# Timer.net
KiCad netlist of a schematic drawn in EAGLE
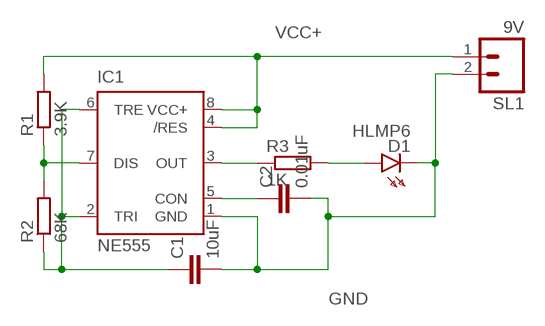
[diagram p0: schematic, sheet 1]

(export (version "E")
  (design (tool "Eeschema 10.0.6"))
  (components
    (comp (ref "C1")
      (value "10uF")
      (footprint "eagle-import:C025-025X050")
      (libsource (lib "eagle-import") (part "C-EU025-025X050"))
    )
    (comp (ref "C2")
      (value "0.01uF")
      (footprint "eagle-import:C025-025X050")
      (libsource (lib "eagle-import") (part "C-EU025-025X050"))
    )
    (comp (ref "D1")
      (value "HLMP6")
      (footprint "eagle-import:HLMP6")
      (fields (field (name "MF") "AGILENT TECHNOLOGIES") (field (name "MPN") "HLMP-6500"))
      (libsource (lib "eagle-import") (part "HLMP6"))
    )
    (comp (ref "IC1")
      (value "NE555")
      (footprint "eagle-import:DIL-08")
      (fields (field (name "MF") "Arrow Electronics") (field (name "MPN") "NE555N"))
      (libsource (lib "eagle-import") (part "NE555"))
    )
    (comp (ref "R1")
      (value "3.9K")
      (footprint "eagle-import:0204_7")
      (libsource (lib "eagle-import") (part "R-EU_0204/7"))
    )
    (comp (ref "R2")
      (value "68K")
      (footprint "eagle-import:0204_7")
      (libsource (lib "eagle-import") (part "R-EU_0204/7"))
    )
    (comp (ref "R3")
      (value "1K")
      (footprint "eagle-import:0204_7")
      (libsource (lib "eagle-import") (part "R-EU_0204/7"))
    )
    (comp (ref "SL1")
      (value "9V")
      (footprint "eagle-import:02P")
      (libsource (lib "eagle-import") (part "M02"))
    )
  )
  (nets
    (net (code "1") (name "/GND") (class "Default")
      (node (ref "C1") (pin "2") (pinfunction "2_2") (pintype "passive"))
      (node (ref "C2") (pin "2") (pinfunction "2_2") (pintype "passive"))
      (node (ref "D1") (pin "K") (pinfunction "K_K") (pintype "passive"))
      (node (ref "IC1") (pin "1") (pinfunction "GND_1") (pintype "power_in"))
      (node (ref "SL1") (pin "2") (pinfunction "2_2") (pintype "passive"))
    )
    (net (code "2") (name "/VCC+") (class "Default")
      (node (ref "IC1") (pin "4") (pinfunction "/RES_4") (pintype "input"))
      (node (ref "IC1") (pin "8") (pinfunction "VCC+_8") (pintype "power_in"))
      (node (ref "R1") (pin "2") (pinfunction "2_2") (pintype "passive"))
      (node (ref "SL1") (pin "1") (pinfunction "1_1") (pintype "passive"))
    )
    (net (code "3") (name "Net-(D1-PadA)") (class "Default")
      (node (ref "D1") (pin "A") (pinfunction "A_A") (pintype "passive"))
      (node (ref "R3") (pin "2") (pinfunction "2_2") (pintype "passive"))
    )
    (net (code "4") (name "Net-(IC1-CON)") (class "Default")
      (node (ref "C2") (pin "1") (pinfunction "1_1") (pintype "passive"))
      (node (ref "IC1") (pin "5") (pinfunction "CON_5") (pintype "input"))
    )
    (net (code "5") (name "Net-(IC1-DIS)") (class "Default")
      (node (ref "IC1") (pin "7") (pinfunction "DIS_7") (pintype "input"))
      (node (ref "R1") (pin "1") (pinfunction "1_1") (pintype "passive"))
      (node (ref "R2") (pin "2") (pinfunction "2_2") (pintype "passive"))
    )
    (net (code "6") (name "Net-(IC1-OUT)") (class "Default")
      (node (ref "IC1") (pin "3") (pinfunction "OUT_3") (pintype "output"))
      (node (ref "R3") (pin "1") (pinfunction "1_1") (pintype "passive"))
    )
    (net (code "7") (name "Net-(IC1-TRE)") (class "Default")
      (node (ref "C1") (pin "1") (pinfunction "1_1") (pintype "passive"))
      (node (ref "IC1") (pin "2") (pinfunction "TRI_2") (pintype "input"))
      (node (ref "IC1") (pin "6") (pinfunction "TRE_6") (pintype "input"))
      (node (ref "R2") (pin "1") (pinfunction "1_1") (pintype "passive"))
    )
  )
)
